# Qwiic_Grideye.net
KiCad netlist of a schematic drawn in EAGLE
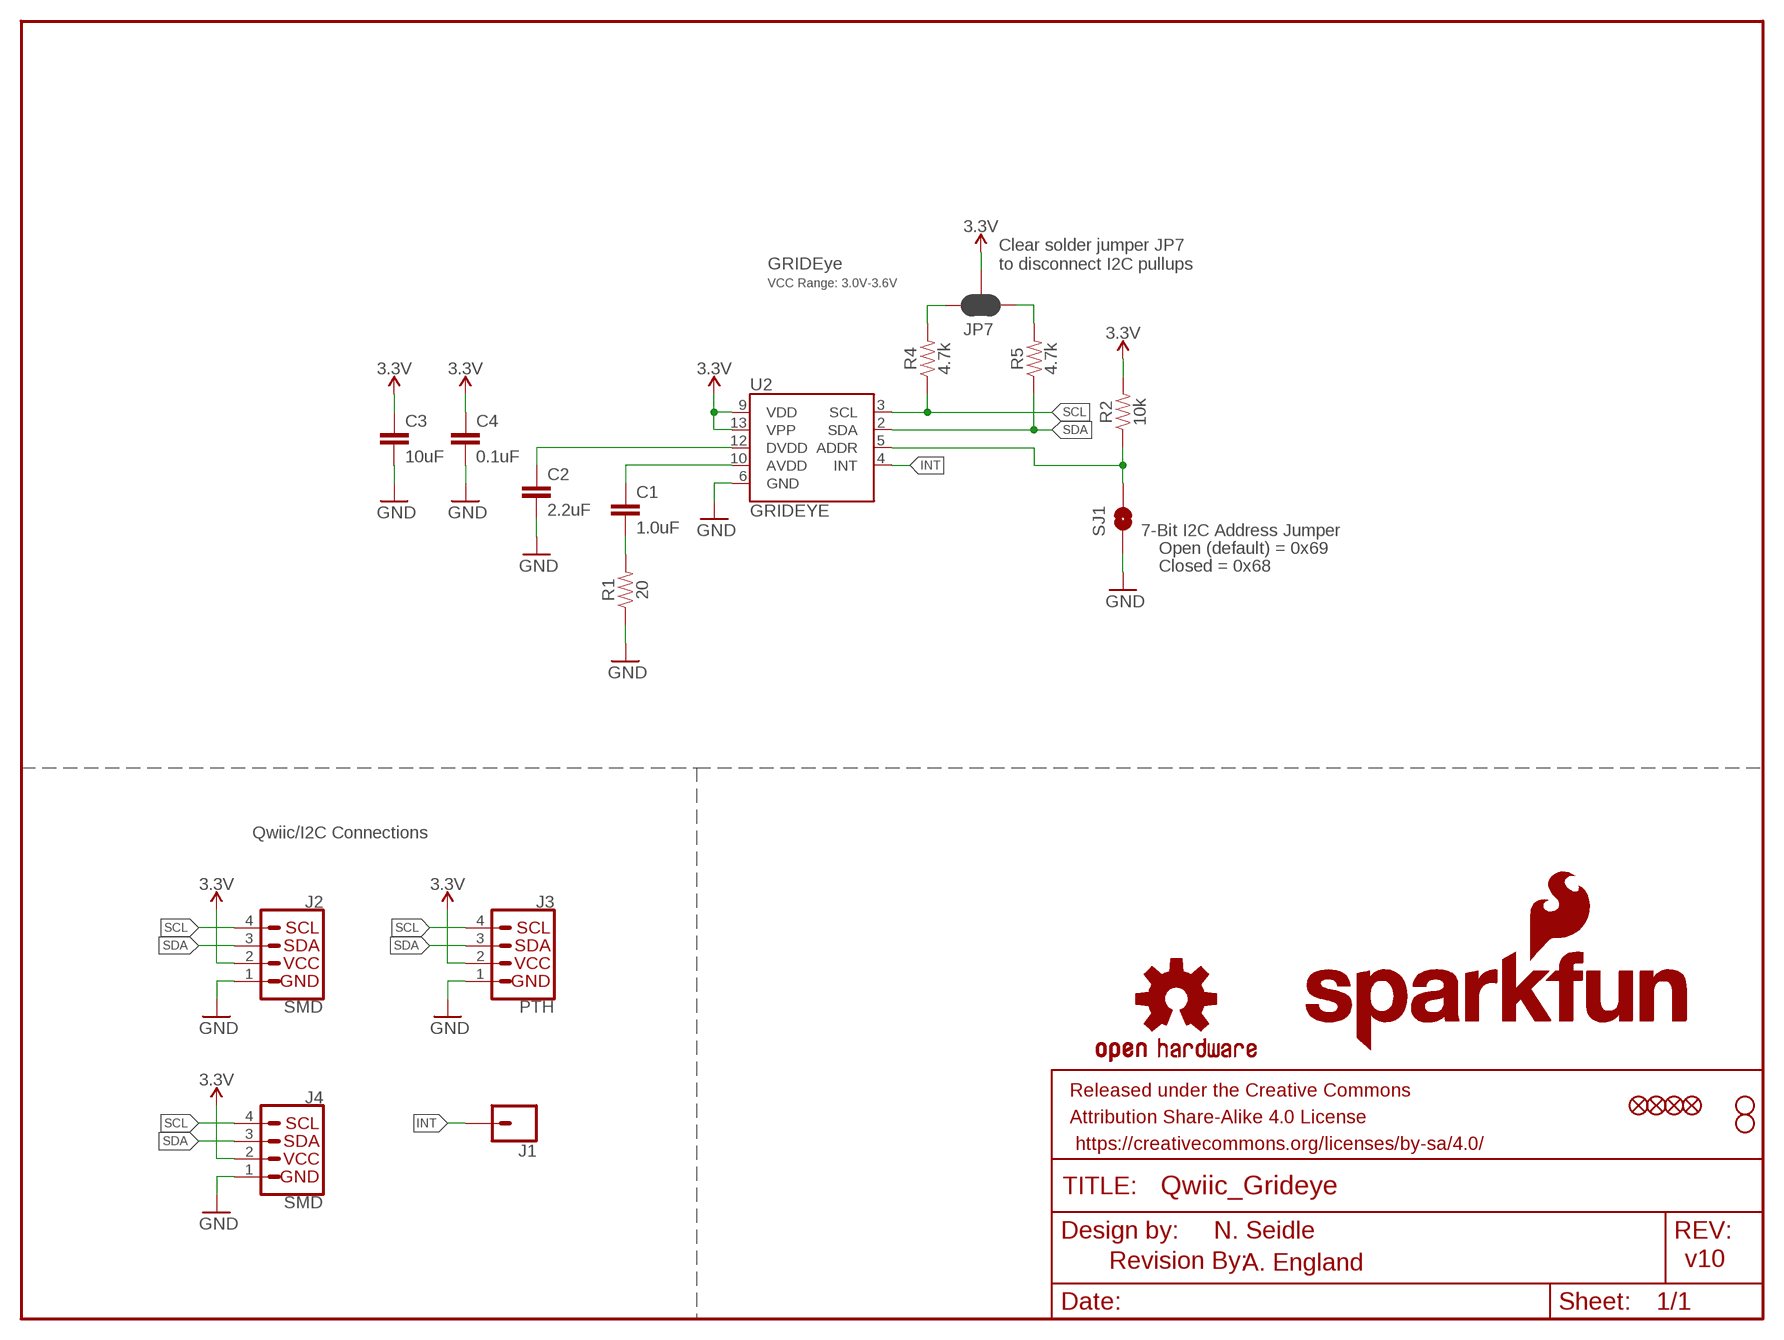
[diagram p0: schematic, sheet 1]

(export (version "E")
  (design (tool "Eeschema 10.0.6"))
  (components
    (comp (ref "C1")
      (value "1.0uF")
      (footprint "eagle-import:0603")
      (libsource (lib "eagle-import") (part "1.0UF-0603-16V-10%"))
    )
    (comp (ref "C2")
      (value "2.2uF")
      (footprint "eagle-import:0603")
      (libsource (lib "eagle-import") (part "2.2UF-0603-10V-20%"))
    )
    (comp (ref "C3")
      (value "10uF")
      (footprint "eagle-import:0603")
      (libsource (lib "eagle-import") (part "10UF-0603-6.3V-20%"))
    )
    (comp (ref "C4")
      (value "0.1uF")
      (footprint "eagle-import:0603")
      (libsource (lib "eagle-import") (part "0.1UF-0603-25V-(+80/-20%)"))
    )
    (comp (ref "FRAME1")
      (value "FRAME-LETTER")
      (footprint "eagle-import:CREATIVE_COMMONS")
      (libsource (lib "eagle-import") (part "FRAME-LETTER"))
    )
    (comp (ref "J1")
      (value "CONN_01PTH_NO_SILK_YES_STOP")
      (footprint "eagle-import:1X01_NO_SILK")
      (libsource (lib "eagle-import") (part "CONN_01PTH_NO_SILK_YES_STOP"))
    )
    (comp (ref "J2")
      (value "SMD")
      (footprint "eagle-import:1X04_1MM_RA")
      (libsource (lib "eagle-import") (part "I2C_STANDARDJS-1MM"))
    )
    (comp (ref "J3")
      (value "PTH")
      (footprint "eagle-import:1X04_NO_SILK")
      (libsource (lib "eagle-import") (part "I2C_STANDARD_NO_SILK"))
    )
    (comp (ref "J4")
      (value "SMD")
      (footprint "eagle-import:1X04_1MM_RA")
      (libsource (lib "eagle-import") (part "I2C_STANDARDJS-1MM"))
    )
    (comp (ref "JP1")
      (value "FIDUCIALUFIDUCIAL")
      (footprint "eagle-import:MICRO-FIDUCIAL")
      (libsource (lib "eagle-import") (part "FIDUCIALUFIDUCIAL"))
    )
    (comp (ref "JP2")
      (value "FIDUCIALUFIDUCIAL")
      (footprint "eagle-import:MICRO-FIDUCIAL")
      (libsource (lib "eagle-import") (part "FIDUCIALUFIDUCIAL"))
    )
    (comp (ref "JP3")
      (value "STAND-OFF")
      (footprint "eagle-import:STAND-OFF")
      (libsource (lib "eagle-import") (part "STAND-OFF"))
    )
    (comp (ref "JP4")
      (value "STAND-OFF")
      (footprint "eagle-import:STAND-OFF")
      (libsource (lib "eagle-import") (part "STAND-OFF"))
    )
    (comp (ref "JP5")
      (value "FIDUCIALUFIDUCIAL")
      (footprint "eagle-import:MICRO-FIDUCIAL")
      (libsource (lib "eagle-import") (part "FIDUCIALUFIDUCIAL"))
    )
    (comp (ref "JP6")
      (value "FIDUCIALUFIDUCIAL")
      (footprint "eagle-import:MICRO-FIDUCIAL")
      (libsource (lib "eagle-import") (part "FIDUCIALUFIDUCIAL"))
    )
    (comp (ref "JP7")
      (value "JUMPER-SMT_3_2-NC_PASTE_SILK")
      (footprint "eagle-import:SMT-JUMPER_3_2-NC_PASTE_SILK")
      (libsource (lib "eagle-import") (part "JUMPER-SMT_3_2-NC_PASTE_SILK"))
    )
    (comp (ref "LOGO1")
      (value "OSHW-LOGOMINI")
      (footprint "eagle-import:OSHW-LOGO-MINI")
      (libsource (lib "eagle-import") (part "OSHW-LOGOMINI"))
    )
    (comp (ref "LOGO2")
      (value "REVISION")
      (footprint "eagle-import:REVISION")
      (libsource (lib "eagle-import") (part "REVISION"))
    )
    (comp (ref "R1")
      (value "20")
      (footprint "eagle-import:0603")
      (libsource (lib "eagle-import") (part "20OHM-0603-1/10W-1%"))
    )
    (comp (ref "R2")
      (value "10k")
      (footprint "eagle-import:0603")
      (libsource (lib "eagle-import") (part "10KOHM-0603-1/10W-1%"))
    )
    (comp (ref "R4")
      (value "4.7k")
      (footprint "eagle-import:0603")
      (libsource (lib "eagle-import") (part "4.7KOHM-0603-1/10W-1%"))
    )
    (comp (ref "R5")
      (value "4.7k")
      (footprint "eagle-import:0603")
      (libsource (lib "eagle-import") (part "4.7KOHM-0603-1/10W-1%"))
    )
    (comp (ref "SJ1")
      (value "SOLDERJUMPERNO")
      (footprint "eagle-import:SJ_2S-NO")
      (libsource (lib "eagle-import") (part "SOLDERJUMPERNO"))
    )
    (comp (ref "U$1")
      (value "SFE_LOGO_NAME.1_INCH")
      (footprint "eagle-import:SFE_LOGO_NAME_.1")
      (libsource (lib "eagle-import") (part "SFE_LOGO_NAME.1_INCH"))
    )
    (comp (ref "U$2")
      (value "SFE_LOGO_NAME_FLAME.1_INCH")
      (footprint "eagle-import:SFE_LOGO_NAME_FLAME_.1")
      (libsource (lib "eagle-import") (part "SFE_LOGO_NAME_FLAME.1_INCH"))
    )
    (comp (ref "U2")
      (value "GRIDEYE")
      (footprint "eagle-import:GRIDEYE-AMG88")
      (libsource (lib "eagle-import") (part "GRIDEYE"))
    )
  )
  (nets
    (net (code "1") (name "3.3V") (class "Default")
      (node (ref "C3") (pin "1") (pinfunction "1_1") (pintype "passive"))
      (node (ref "C4") (pin "1") (pinfunction "1_1") (pintype "passive"))
      (node (ref "J2") (pin "2") (pinfunction "VCC_2") (pintype "power_in"))
      (node (ref "J3") (pin "2") (pinfunction "VCC_2") (pintype "power_in"))
      (node (ref "J4") (pin "2") (pinfunction "VCC_2") (pintype "power_in"))
      (node (ref "JP7") (pin "2") (pinfunction "2_2") (pintype "passive"))
      (node (ref "R2") (pin "2") (pinfunction "2_2") (pintype "passive"))
      (node (ref "U2") (pin "13") (pinfunction "VPP_13") (pintype "bidirectional"))
      (node (ref "U2") (pin "9") (pinfunction "VDD_9") (pintype "bidirectional"))
    )
    (net (code "2") (name "GND") (class "Default")
      (node (ref "C2") (pin "2") (pinfunction "2_2") (pintype "passive"))
      (node (ref "C3") (pin "2") (pinfunction "2_2") (pintype "passive"))
      (node (ref "C4") (pin "2") (pinfunction "2_2") (pintype "passive"))
      (node (ref "J2") (pin "1") (pinfunction "GND_1") (pintype "power_in"))
      (node (ref "J3") (pin "1") (pinfunction "GND_1") (pintype "power_in"))
      (node (ref "J4") (pin "1") (pinfunction "GND_1") (pintype "power_in"))
      (node (ref "R1") (pin "1") (pinfunction "1_1") (pintype "passive"))
      (node (ref "SJ1") (pin "1") (pinfunction "1_1") (pintype "passive"))
      (node (ref "U2") (pin "6") (pinfunction "GND_6") (pintype "bidirectional"))
    )
    (net (code "3") (name "INT") (class "Default")
      (node (ref "J1") (pin "1") (pinfunction "1_1") (pintype "passive"))
      (node (ref "U2") (pin "4") (pinfunction "INT_4") (pintype "bidirectional"))
    )
    (net (code "4") (name "Net-(C1-Pad2)") (class "Default")
      (node (ref "C1") (pin "2") (pinfunction "2_2") (pintype "passive"))
      (node (ref "R1") (pin "2") (pinfunction "2_2") (pintype "passive"))
    )
    (net (code "5") (name "Net-(JP7-Pad1)") (class "Default")
      (node (ref "JP7") (pin "1") (pinfunction "1_1") (pintype "passive"))
      (node (ref "R5") (pin "2") (pinfunction "2_2") (pintype "passive"))
    )
    (net (code "6") (name "Net-(JP7-Pad3)") (class "Default")
      (node (ref "JP7") (pin "3") (pinfunction "3_3") (pintype "passive"))
      (node (ref "R4") (pin "2") (pinfunction "2_2") (pintype "passive"))
    )
    (net (code "7") (name "Net-(U2-ADDR)") (class "Default")
      (node (ref "R2") (pin "1") (pinfunction "1_1") (pintype "passive"))
      (node (ref "SJ1") (pin "2") (pinfunction "2_2") (pintype "passive"))
      (node (ref "U2") (pin "5") (pinfunction "ADDR_5") (pintype "bidirectional"))
    )
    (net (code "8") (name "Net-(U2-AVDD)") (class "Default")
      (node (ref "C1") (pin "1") (pinfunction "1_1") (pintype "passive"))
      (node (ref "U2") (pin "10") (pinfunction "AVDD_10") (pintype "bidirectional"))
    )
    (net (code "9") (name "Net-(U2-DVDD)") (class "Default")
      (node (ref "C2") (pin "1") (pinfunction "1_1") (pintype "passive"))
      (node (ref "U2") (pin "12") (pinfunction "DVDD_12") (pintype "bidirectional"))
    )
    (net (code "10") (name "SCL") (class "Default")
      (node (ref "J2") (pin "4") (pinfunction "SCL_4") (pintype "passive"))
      (node (ref "J3") (pin "4") (pinfunction "SCL_4") (pintype "passive"))
      (node (ref "J4") (pin "4") (pinfunction "SCL_4") (pintype "passive"))
      (node (ref "R4") (pin "1") (pinfunction "1_1") (pintype "passive"))
      (node (ref "U2") (pin "3") (pinfunction "SCL_3") (pintype "bidirectional"))
    )
    (net (code "11") (name "SDA") (class "Default")
      (node (ref "J2") (pin "3") (pinfunction "SDA_3") (pintype "passive"))
      (node (ref "J3") (pin "3") (pinfunction "SDA_3") (pintype "passive"))
      (node (ref "J4") (pin "3") (pinfunction "SDA_3") (pintype "passive"))
      (node (ref "R5") (pin "1") (pinfunction "1_1") (pintype "passive"))
      (node (ref "U2") (pin "2") (pinfunction "SDA_2") (pintype "bidirectional"))
    )
  )
)
